# Power_Analyzer.net
KiCad netlist of a schematic drawn in EasyEDA Pro
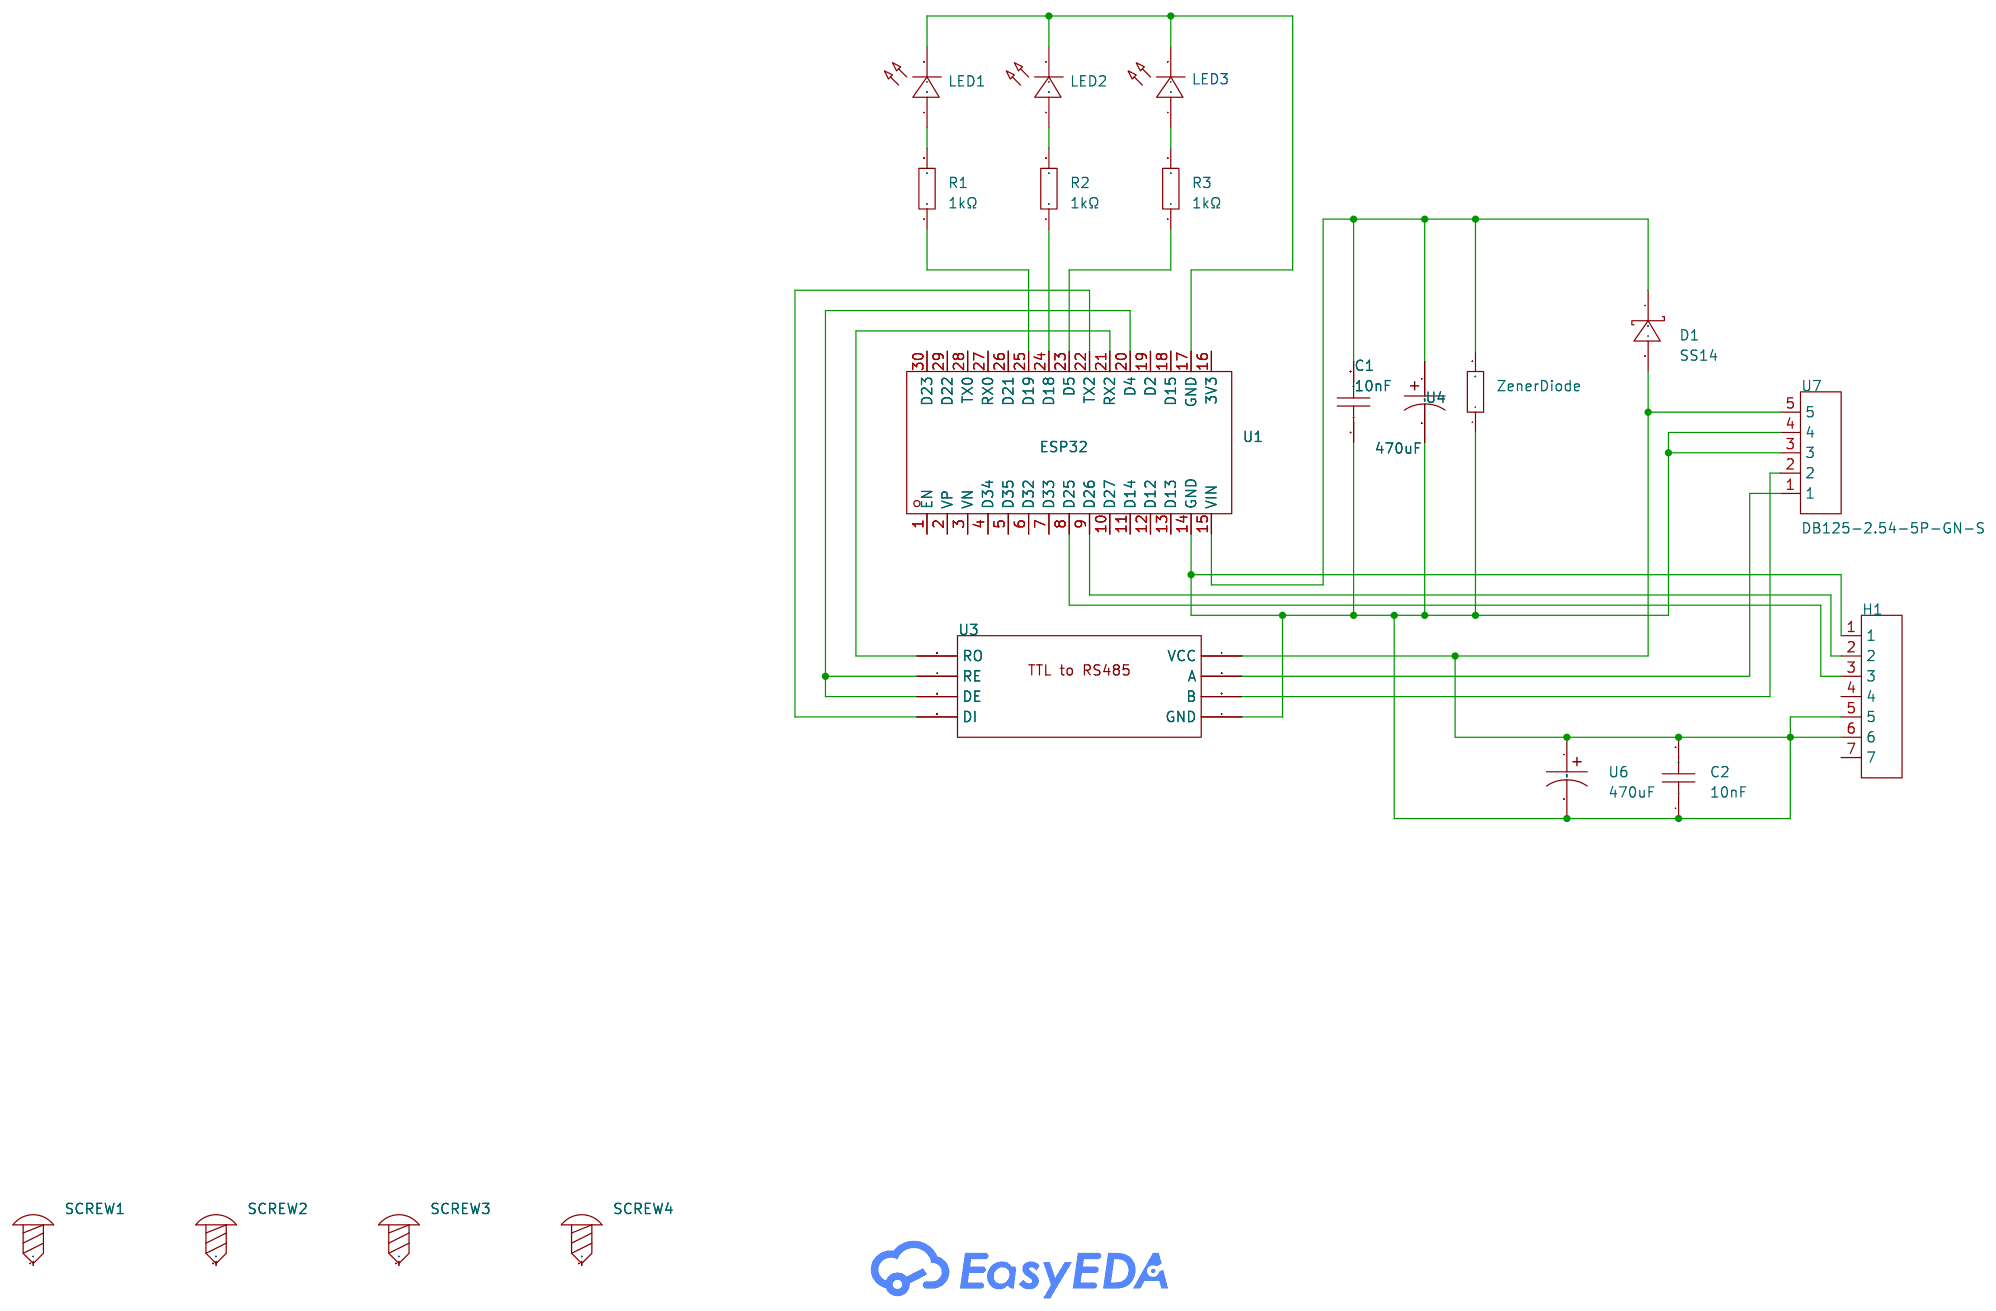
[diagram p0: schematic sheet]

(export (version "E")
  (design (tool "Eeschema 10.0.6"))
  (components
    (comp (ref "C1")
      (value "10nF")
      (footprint "easyedapro:CAP-TH_L4.9-W3.7-P5.08-D0.5")
      (description "Capacitance:10nF Tolerance:±5% Tolerance:±5% Voltage Rating:50V Temperature Coefficient:-")
      (fields
        (field (name "Manufacturer Part") "CC4-0805-CG-50V-0.01μF-J")
        (field (name "Manufacturer") "TORCH(火炬)")
      )
      (libsource (lib "easyedapro") (part "CC4-0805-CG-50V-0.01μF-J"))
    )
    (comp (ref "C2")
      (value "10nF")
      (footprint "easyedapro:CAP-TH_L4.9-W3.7-P5.08-D0.5")
      (description "Capacitance:10nF Tolerance:±5% Tolerance:±5% Voltage Rating:50V Temperature Coefficient:-")
      (fields
        (field (name "Manufacturer Part") "CC4-0805-CG-50V-0.01μF-J")
        (field (name "Manufacturer") "TORCH(火炬)")
      )
      (libsource (lib "easyedapro") (part "CC4-0805-CG-50V-0.01μF-J"))
    )
    (comp (ref "D1")
      (value "SS14")
      (footprint "easyedapro:SMA_L4.2-W2.6-LS5.3-RD")
      (description "Voltage - Forward(Vf@If):550mV@1A Voltage - DC Reverse(Vr):40V Current - Rectified:1A")
      (fields (field (name "Manufacturer") "High Diode(海德)"))
      (libsource (lib "easyedapro") (part "SS14_C466498"))
    )
    (comp (ref "H1")
      (value "~")
      (footprint "easyedapro:HDR-TH_7P-P2.54-V-M")
      (libsource (lib "easyedapro") (part "PZ254V-11-07P"))
    )
    (comp (ref "LED1")
      (value "~")
      (footprint "easyedapro:LED-TH_BD3.0-P2.54-FD")
      (libsource (lib "easyedapro") (part "LED_TH-R"))
    )
    (comp (ref "LED2")
      (value "~")
      (footprint "easyedapro:LED-TH_BD3.0-P2.54-FD")
      (libsource (lib "easyedapro") (part "LED_TH-R"))
    )
    (comp (ref "LED3")
      (value "~")
      (footprint "easyedapro:LED-TH_BD3.0-P2.54-FD")
      (libsource (lib "easyedapro") (part "LED_TH-R"))
    )
    (comp (ref "R1") (value "1kΩ") (footprint "easyedapro:R0603") (libsource (lib "easyedapro") (part "Res")))
    (comp (ref "R2") (value "1kΩ") (footprint "easyedapro:R0603") (libsource (lib "easyedapro") (part "Res")))
    (comp (ref "R3") (value "1kΩ") (footprint "easyedapro:R0603") (libsource (lib "easyedapro") (part "Res")))
    (comp (ref "SCREW1")
      (value "~")
      (footprint "easyedapro:Screw-Hole-M2")
      (libsource (lib "easyedapro") (part "Screw-Hole"))
    )
    (comp (ref "SCREW2")
      (value "~")
      (footprint "easyedapro:Screw-Hole-M2")
      (libsource (lib "easyedapro") (part "Screw-Hole"))
    )
    (comp (ref "SCREW3")
      (value "~")
      (footprint "easyedapro:Screw-Hole-M2")
      (libsource (lib "easyedapro") (part "Screw-Hole"))
    )
    (comp (ref "SCREW4")
      (value "~")
      (footprint "easyedapro:Screw-Hole-M2")
      (libsource (lib "easyedapro") (part "Screw-Hole"))
    )
    (comp (ref "U1")
      (value "ESP32")
      (footprint "easyedapro:COMM-TH_L43.7-W25.4-P2.54_NODEMCU")
      (fields (field (name "Manufacturer") "Ai-Thinker(安信可)"))
      (libsource (lib "easyedapro") (part "NODEMCU(12S)"))
    )
    (comp (ref "U3")
      (value "~")
      (footprint "easyedapro:HDR-TH_8P-P2.54-V-F-R2-C4-S2.54-1")
      (libsource (lib "easyedapro") (part "HDR-F-2.54_2x4"))
    )
    (comp (ref "U4")
      (value "470uF")
      (footprint "easyedapro:CAP-TH_BD8.0-P3.50-D0.5-FD")
      (fields (field (name "Manufacturer Part") "25V470uF CD110") (field (name "Manufacturer") "HRK(鸿瑞凯电子)"))
      (libsource (lib "easyedapro") (part "25V470UF CD110"))
    )
    (comp (ref "U6")
      (value "470uF")
      (footprint "easyedapro:CAP-TH_BD8.0-P3.50-D0.5-FD")
      (fields (field (name "Manufacturer Part") "25V470uF CD110") (field (name "Manufacturer") "HRK(鸿瑞凯电子)"))
      (libsource (lib "easyedapro") (part "25V470UF CD110"))
    )
    (comp (ref "U7")
      (value "DB125-2.54-5P-GN-S")
      (footprint "easyedapro:CONN-TH_DB125-2.54-5P-GN")
      (fields (field (name "Manufacturer") "DORABO(地博电气)"))
      (libsource (lib "easyedapro") (part "DB125-2.54-5P-GN"))
    )
    (comp (ref "ZenerDiode")
      (value "10kΩ")
      (footprint "easyedapro:R0603")
      (libsource (lib "easyedapro") (part "Res"))
    )
  )
  (nets
    (net (code "1") (name "Net-(D1-A)") (class "Default")
      (node (ref "C1") (pin "1") (pinfunction "1_1") (pintype "unspecified"))
      (node (ref "C2") (pin "1") (pinfunction "1_1") (pintype "unspecified"))
      (node (ref "C2") (pin "2") (pinfunction "2_2") (pintype "unspecified"))
      (node (ref "D1") (pin "2") (pinfunction "A_2") (pintype "unspecified"))
      (node (ref "H1") (pin "1") (pinfunction "1_1") (pintype "unspecified"))
      (node (ref "H1") (pin "5") (pinfunction "5_5") (pintype "unspecified"))
      (node (ref "H1") (pin "6") (pinfunction "6_6") (pintype "unspecified"))
      (node (ref "U1") (pin "14") (pinfunction "GND_14") (pintype "unspecified"))
      (node (ref "U3") (pin "1") (pinfunction "GND_1") (pintype "input"))
      (node (ref "U3") (pin "4") (pinfunction "VCC_4") (pintype "input"))
      (node (ref "U4") (pin "2") (pinfunction "2_2") (pintype "unspecified"))
      (node (ref "U6") (pin "1") (pinfunction "1_1") (pintype "unspecified"))
      (node (ref "U6") (pin "2") (pinfunction "2_2") (pintype "unspecified"))
      (node (ref "U7") (pin "3") (pinfunction "3_3") (pintype "unspecified"))
      (node (ref "U7") (pin "4") (pinfunction "4_4") (pintype "unspecified"))
      (node (ref "U7") (pin "5") (pinfunction "5_5") (pintype "unspecified"))
      (node (ref "ZenerDiode") (pin "1") (pinfunction "1_1") (pintype "input"))
    )
    (net (code "2") (name "Net-(D1-C)") (class "Default")
      (node (ref "C1") (pin "2") (pinfunction "2_2") (pintype "unspecified"))
      (node (ref "D1") (pin "1") (pinfunction "C_1") (pintype "unspecified"))
      (node (ref "U1") (pin "15") (pinfunction "VIN_15") (pintype "unspecified"))
      (node (ref "U4") (pin "1") (pinfunction "1_1") (pintype "unspecified"))
      (node (ref "ZenerDiode") (pin "2") (pinfunction "2_2") (pintype "input"))
    )
    (net (code "3") (name "Net-(LED1-A)") (class "Default")
      (node (ref "LED1") (pin "2") (pinfunction "A_2") (pintype "input"))
      (node (ref "LED2") (pin "2") (pinfunction "A_2") (pintype "input"))
      (node (ref "LED3") (pin "2") (pinfunction "A_2") (pintype "input"))
      (node (ref "U1") (pin "17") (pinfunction "GND_17") (pintype "unspecified"))
    )
    (net (code "4") (name "Net-(LED1-C)") (class "Default")
      (node (ref "LED1") (pin "1") (pinfunction "C_1") (pintype "input"))
      (node (ref "R1") (pin "2") (pinfunction "2_2") (pintype "input"))
    )
    (net (code "5") (name "Net-(LED2-C)") (class "Default")
      (node (ref "LED2") (pin "1") (pinfunction "C_1") (pintype "input"))
      (node (ref "R2") (pin "2") (pinfunction "2_2") (pintype "input"))
    )
    (net (code "6") (name "Net-(LED3-C)") (class "Default")
      (node (ref "LED3") (pin "1") (pinfunction "C_1") (pintype "input"))
      (node (ref "R3") (pin "2") (pinfunction "2_2") (pintype "input"))
    )
    (net (code "7") (name "Net-(U1-D4)") (class "Default")
      (node (ref "U1") (pin "20") (pinfunction "D4_20") (pintype "unspecified"))
      (node (ref "U3") (pin "6") (pinfunction "DE_6") (pintype "input"))
      (node (ref "U3") (pin "7") (pinfunction "RE_7") (pintype "input"))
    )
    (net (code "8") (name "Net-(U1-D5)") (class "Default")
      (node (ref "R3") (pin "1") (pinfunction "1_1") (pintype "input"))
      (node (ref "U1") (pin "23") (pinfunction "D5_23") (pintype "unspecified"))
    )
    (net (code "9") (name "Net-(U1-D18)") (class "Default")
      (node (ref "R2") (pin "1") (pinfunction "1_1") (pintype "input"))
      (node (ref "U1") (pin "24") (pinfunction "D18_24") (pintype "unspecified"))
    )
    (net (code "10") (name "Net-(U1-D19)") (class "Default")
      (node (ref "R1") (pin "1") (pinfunction "1_1") (pintype "input"))
      (node (ref "U1") (pin "25") (pinfunction "D19_25") (pintype "unspecified"))
    )
    (net (code "11") (name "Net-(U1-D25)") (class "Default")
      (node (ref "H1") (pin "3") (pinfunction "3_3") (pintype "unspecified"))
      (node (ref "U1") (pin "8") (pinfunction "D25_8") (pintype "unspecified"))
    )
    (net (code "12") (name "Net-(U1-D26)") (class "Default")
      (node (ref "H1") (pin "2") (pinfunction "2_2") (pintype "unspecified"))
      (node (ref "U1") (pin "9") (pinfunction "D26_9") (pintype "unspecified"))
    )
    (net (code "13") (name "Net-(U1-RX2)") (class "Default")
      (node (ref "U1") (pin "21") (pinfunction "RX2_21") (pintype "unspecified"))
      (node (ref "U3") (pin "8") (pinfunction "RO_8") (pintype "input"))
    )
    (net (code "14") (name "Net-(U1-TX2)") (class "Default")
      (node (ref "U1") (pin "22") (pinfunction "TX2_22") (pintype "unspecified"))
      (node (ref "U3") (pin "5") (pinfunction "DI_5") (pintype "input"))
    )
    (net (code "15") (name "Net-(U3-A)") (class "Default")
      (node (ref "U3") (pin "3") (pinfunction "A_3") (pintype "input"))
      (node (ref "U7") (pin "1") (pinfunction "1_1") (pintype "unspecified"))
    )
    (net (code "16") (name "Net-(U3-B)") (class "Default")
      (node (ref "U3") (pin "2") (pinfunction "B_2") (pintype "input"))
      (node (ref "U7") (pin "2") (pinfunction "2_2") (pintype "unspecified"))
    )
    (net (code "17") (name "unconnected-(H1-Pad4)") (class "Default")
      (node (ref "H1") (pin "4") (pinfunction "4_4") (pintype "unspecified"))
    )
    (net (code "18") (name "unconnected-(H1-Pad7)") (class "Default")
      (node (ref "H1") (pin "7") (pinfunction "7_7") (pintype "unspecified"))
    )
    (net (code "19") (name "unconnected-(SCREW1-Pad1)") (class "Default")
      (node (ref "SCREW1") (pin "1") (pinfunction "1_1") (pintype "input"))
    )
    (net (code "20") (name "unconnected-(SCREW2-Pad1)") (class "Default")
      (node (ref "SCREW2") (pin "1") (pinfunction "1_1") (pintype "input"))
    )
    (net (code "21") (name "unconnected-(SCREW3-Pad1)") (class "Default")
      (node (ref "SCREW3") (pin "1") (pinfunction "1_1") (pintype "input"))
    )
    (net (code "22") (name "unconnected-(SCREW4-Pad1)") (class "Default")
      (node (ref "SCREW4") (pin "1") (pinfunction "1_1") (pintype "input"))
    )
    (net (code "23") (name "unconnected-(U1-3V3-Pad16)") (class "Default")
      (node (ref "U1") (pin "16") (pinfunction "3V3_16") (pintype "unspecified"))
    )
    (net (code "24") (name "unconnected-(U1-D2-Pad19)") (class "Default")
      (node (ref "U1") (pin "19") (pinfunction "D2_19") (pintype "unspecified"))
    )
    (net (code "25") (name "unconnected-(U1-D12-Pad12)") (class "Default")
      (node (ref "U1") (pin "12") (pinfunction "D12_12") (pintype "unspecified"))
    )
    (net (code "26") (name "unconnected-(U1-D13-Pad13)") (class "Default")
      (node (ref "U1") (pin "13") (pinfunction "D13_13") (pintype "unspecified"))
    )
    (net (code "27") (name "unconnected-(U1-D14-Pad11)") (class "Default")
      (node (ref "U1") (pin "11") (pinfunction "D14_11") (pintype "unspecified"))
    )
    (net (code "28") (name "unconnected-(U1-D15-Pad18)") (class "Default")
      (node (ref "U1") (pin "18") (pinfunction "D15_18") (pintype "unspecified"))
    )
    (net (code "29") (name "unconnected-(U1-D21-Pad26)") (class "Default")
      (node (ref "U1") (pin "26") (pinfunction "D21_26") (pintype "unspecified"))
    )
    (net (code "30") (name "unconnected-(U1-D22-Pad29)") (class "Default")
      (node (ref "U1") (pin "29") (pinfunction "D22_29") (pintype "unspecified"))
    )
    (net (code "31") (name "unconnected-(U1-D23-Pad30)") (class "Default")
      (node (ref "U1") (pin "30") (pinfunction "D23_30") (pintype "unspecified"))
    )
    (net (code "32") (name "unconnected-(U1-D27-Pad10)") (class "Default")
      (node (ref "U1") (pin "10") (pinfunction "D27_10") (pintype "unspecified"))
    )
    (net (code "33") (name "unconnected-(U1-D32-Pad6)") (class "Default")
      (node (ref "U1") (pin "6") (pinfunction "D32_6") (pintype "unspecified"))
    )
    (net (code "34") (name "unconnected-(U1-D33-Pad7)") (class "Default")
      (node (ref "U1") (pin "7") (pinfunction "D33_7") (pintype "unspecified"))
    )
    (net (code "35") (name "unconnected-(U1-D34-Pad4)") (class "Default")
      (node (ref "U1") (pin "4") (pinfunction "D34_4") (pintype "unspecified"))
    )
    (net (code "36") (name "unconnected-(U1-D35-Pad5)") (class "Default")
      (node (ref "U1") (pin "5") (pinfunction "D35_5") (pintype "unspecified"))
    )
    (net (code "37") (name "unconnected-(U1-EN-Pad1)") (class "Default")
      (node (ref "U1") (pin "1") (pinfunction "EN_1") (pintype "unspecified"))
    )
    (net (code "38") (name "unconnected-(U1-RX0-Pad27)") (class "Default")
      (node (ref "U1") (pin "27") (pinfunction "RX0_27") (pintype "unspecified"))
    )
    (net (code "39") (name "unconnected-(U1-TX0-Pad28)") (class "Default")
      (node (ref "U1") (pin "28") (pinfunction "TX0_28") (pintype "unspecified"))
    )
    (net (code "40") (name "unconnected-(U1-VN-Pad3)") (class "Default")
      (node (ref "U1") (pin "3") (pinfunction "VN_3") (pintype "unspecified"))
    )
    (net (code "41") (name "unconnected-(U1-VP-Pad2)") (class "Default")
      (node (ref "U1") (pin "2") (pinfunction "VP_2") (pintype "unspecified"))
    )
  )
)
